# 15-DistanceSRF05.net
KiCad netlist of a schematic drawn in Altium Designer
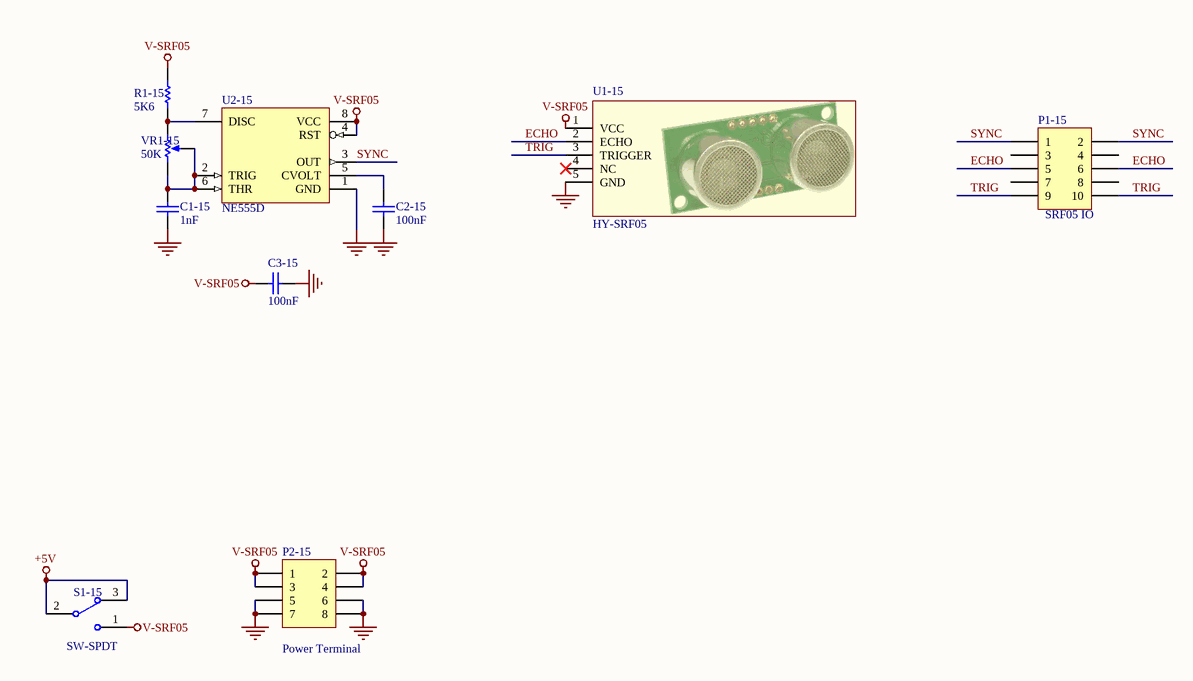
[diagram p0: 15-DistanceSRF05.SchDoc]

(export (version "E")
  (design (tool "Eeschema 10.0.6"))
  (components
    (comp (ref "C1-15")
      (value "1nF")
      (footprint "c-0805")
      (description "Capacitor")
      (fields (field (name "Comment") "102") (field (name "PUBLISHER") "Altium Limited"))
      (libsource (lib "Miscellaneous Devices") (part "Cap"))
    )
    (comp (ref "C2-15")
      (value "100nF")
      (footprint "c-0805")
      (description "Capacitor")
      (fields (field (name "Comment") "104") (field (name "PUBLISHER") "Altium Limited"))
      (libsource (lib "Miscellaneous Devices") (part "Cap"))
    )
    (comp (ref "C3-15")
      (value "100nF")
      (footprint "c-0805")
      (description "Capacitor")
      (fields (field (name "Comment") "104") (field (name "PUBLISHER") "Altium Limited"))
      (libsource (lib "Miscellaneous Devices") (part "Cap"))
    )
    (comp (ref "P1-15")
      (value "SRF05 IO")
      (footprint "JP2.54-F-2x05A")
      (description "Header, 5-Pin, Dual row")
      (fields (field (name "Comment") "Header 5X2"))
      (libsource (lib "Miscellaneous Connectors") (part "Header 5X2"))
    )
    (comp (ref "P2-15")
      (value "Header 4X2")
      (footprint "JP2.54-F-2x04A")
      (description "Header, 4-Pin, Dual row")
      (fields (field (name "PUBLISHER") "Power Terminal"))
      (libsource (lib "Miscellaneous Connectors") (part "Header 4X2"))
    )
    (comp (ref "R1-15")
      (value "5K6")
      (footprint "R-0805")
      (description "Resistor")
      (fields (field (name "Comment") "562") (field (name "PUBLISHER") "Altium Limited"))
      (libsource (lib "Miscellaneous Devices") (part "Res1"))
    )
    (comp (ref "S1-15")
      (value "SW-SPDT")
      (footprint "SW-SLIDE-2P-2W")
      (description "SPDT Subminiature Toggle Switch, Right Angle Mounting, Vertical Actuation")
      (fields (field (name "PUBLISHER") "Altium Limited"))
      (libsource (lib "Miscellaneous Devices") (part "SW-SPDT"))
    )
    (comp (ref "U1-15")
      (value "HY-SRF05")
      (footprint "MDL-SRF05A")
      (libsource (lib "nhoccon1") (part "HY-SRF05"))
    )
    (comp (ref "U2-15")
      (value "NE555D")
      (footprint "SOIC-8")
      (description "General-Purpose Single Bipolar Timer")
      (fields (field (name "PUBLISHER") "Altium Limited"))
      (libsource (lib "ST Analog Timer Circuit") (part "NE555D"))
    )
    (comp (ref "VR1-15")
      (value "50K")
      (footprint "VR-3362P")
      (description "Potentiometer")
      (fields (field (name "PUBLISHER") "Altium Limited"))
      (libsource (lib "Miscellaneous Devices") (part "RPot"))
    )
  )
  (nets
    (net (code "1") (name "+5V") (class "Default")
      (node (ref "S1-15") (pin "2") (pinfunction "2_2") (pintype "passive"))
      (node (ref "S1-15") (pin "3") (pinfunction "3_3") (pintype "passive"))
    )
    (net (code "2") (name "/ECHO") (class "Default")
      (node (ref "P1-15") (pin "5") (pinfunction "5_5") (pintype "passive"))
      (node (ref "P1-15") (pin "6") (pinfunction "6_6") (pintype "passive"))
      (node (ref "U1-15") (pin "2") (pinfunction "ECHO_2") (pintype "passive"))
    )
    (net (code "3") (name "/SYNC") (class "Default")
      (node (ref "P1-15") (pin "1") (pinfunction "1_1") (pintype "passive"))
      (node (ref "P1-15") (pin "2") (pinfunction "2_2") (pintype "passive"))
      (node (ref "U2-15") (pin "3") (pinfunction "OUT_3") (pintype "output"))
    )
    (net (code "4") (name "/TRIG") (class "Default")
      (node (ref "P1-15") (pin "10") (pinfunction "10_10") (pintype "passive"))
      (node (ref "P1-15") (pin "9") (pinfunction "9_9") (pintype "passive"))
      (node (ref "U1-15") (pin "3") (pinfunction "TRIGGER_3") (pintype "passive"))
    )
    (net (code "5") (name "GND") (class "Default")
      (node (ref "C1-15") (pin "1") (pinfunction "1_1") (pintype "passive"))
      (node (ref "C2-15") (pin "1") (pinfunction "1_1") (pintype "passive"))
      (node (ref "C3-15") (pin "1") (pinfunction "1_1") (pintype "passive"))
      (node (ref "P2-15") (pin "5") (pinfunction "5_5") (pintype "passive"))
      (node (ref "P2-15") (pin "6") (pinfunction "6_6") (pintype "passive"))
      (node (ref "P2-15") (pin "7") (pinfunction "7_7") (pintype "passive"))
      (node (ref "P2-15") (pin "8") (pinfunction "8_8") (pintype "passive"))
      (node (ref "U1-15") (pin "5") (pinfunction "GND_5") (pintype "passive"))
      (node (ref "U2-15") (pin "1") (pinfunction "GND_1") (pintype "power_in"))
    )
    (net (code "6") (name "Net-(U2-15-CVOLT)") (class "Default")
      (node (ref "C2-15") (pin "2") (pinfunction "2_2") (pintype "passive"))
      (node (ref "U2-15") (pin "5") (pinfunction "CVOLT_5") (pintype "passive"))
    )
    (net (code "7") (name "Net-(U2-15-DISC)") (class "Default")
      (node (ref "R1-15") (pin "1") (pinfunction "1_1") (pintype "passive"))
      (node (ref "U2-15") (pin "7") (pinfunction "DISC_7") (pintype "open_collector"))
      (node (ref "VR1-15") (pin "3") (pinfunction "BOT_3") (pintype "passive"))
    )
    (net (code "8") (name "Net-(U2-15-THR)") (class "Default")
      (node (ref "C1-15") (pin "2") (pinfunction "2_2") (pintype "passive"))
      (node (ref "U2-15") (pin "2") (pinfunction "TRIG_2") (pintype "input"))
      (node (ref "U2-15") (pin "6") (pinfunction "THR_6") (pintype "input"))
      (node (ref "VR1-15") (pin "1") (pinfunction "TOP_1") (pintype "passive"))
      (node (ref "VR1-15") (pin "2") (pinfunction "TAP_2") (pintype "passive"))
    )
    (net (code "9") (name "V-SRF05") (class "Default")
      (node (ref "C3-15") (pin "2") (pinfunction "2_2") (pintype "passive"))
      (node (ref "P2-15") (pin "1") (pinfunction "1_1") (pintype "passive"))
      (node (ref "P2-15") (pin "2") (pinfunction "2_2") (pintype "passive"))
      (node (ref "P2-15") (pin "3") (pinfunction "3_3") (pintype "passive"))
      (node (ref "P2-15") (pin "4") (pinfunction "4_4") (pintype "passive"))
      (node (ref "R1-15") (pin "2") (pinfunction "2_2") (pintype "passive"))
      (node (ref "S1-15") (pin "1") (pinfunction "1_1") (pintype "passive"))
      (node (ref "U1-15") (pin "1") (pinfunction "VCC_1") (pintype "passive"))
      (node (ref "U2-15") (pin "4") (pinfunction "RST_4") (pintype "input"))
      (node (ref "U2-15") (pin "8") (pinfunction "VCC_8") (pintype "power_in"))
    )
    (net (code "10") (name "unconnected-(P1-15-Pad3)") (class "Default")
      (node (ref "P1-15") (pin "3") (pinfunction "3_3") (pintype "passive"))
    )
    (net (code "11") (name "unconnected-(P1-15-Pad4)") (class "Default")
      (node (ref "P1-15") (pin "4") (pinfunction "4_4") (pintype "passive"))
    )
    (net (code "12") (name "unconnected-(P1-15-Pad7)") (class "Default")
      (node (ref "P1-15") (pin "7") (pinfunction "7_7") (pintype "passive"))
    )
    (net (code "13") (name "unconnected-(P1-15-Pad8)") (class "Default")
      (node (ref "P1-15") (pin "8") (pinfunction "8_8") (pintype "passive"))
    )
    (net (code "14") (name "unconnected-(U1-15-NC-Pad4)") (class "Default")
      (node (ref "U1-15") (pin "4") (pinfunction "NC_4") (pintype "passive+no_connect"))
    )
  )
)
